# Sheet1.net
KiCad netlist of a schematic drawn in Altium Designer
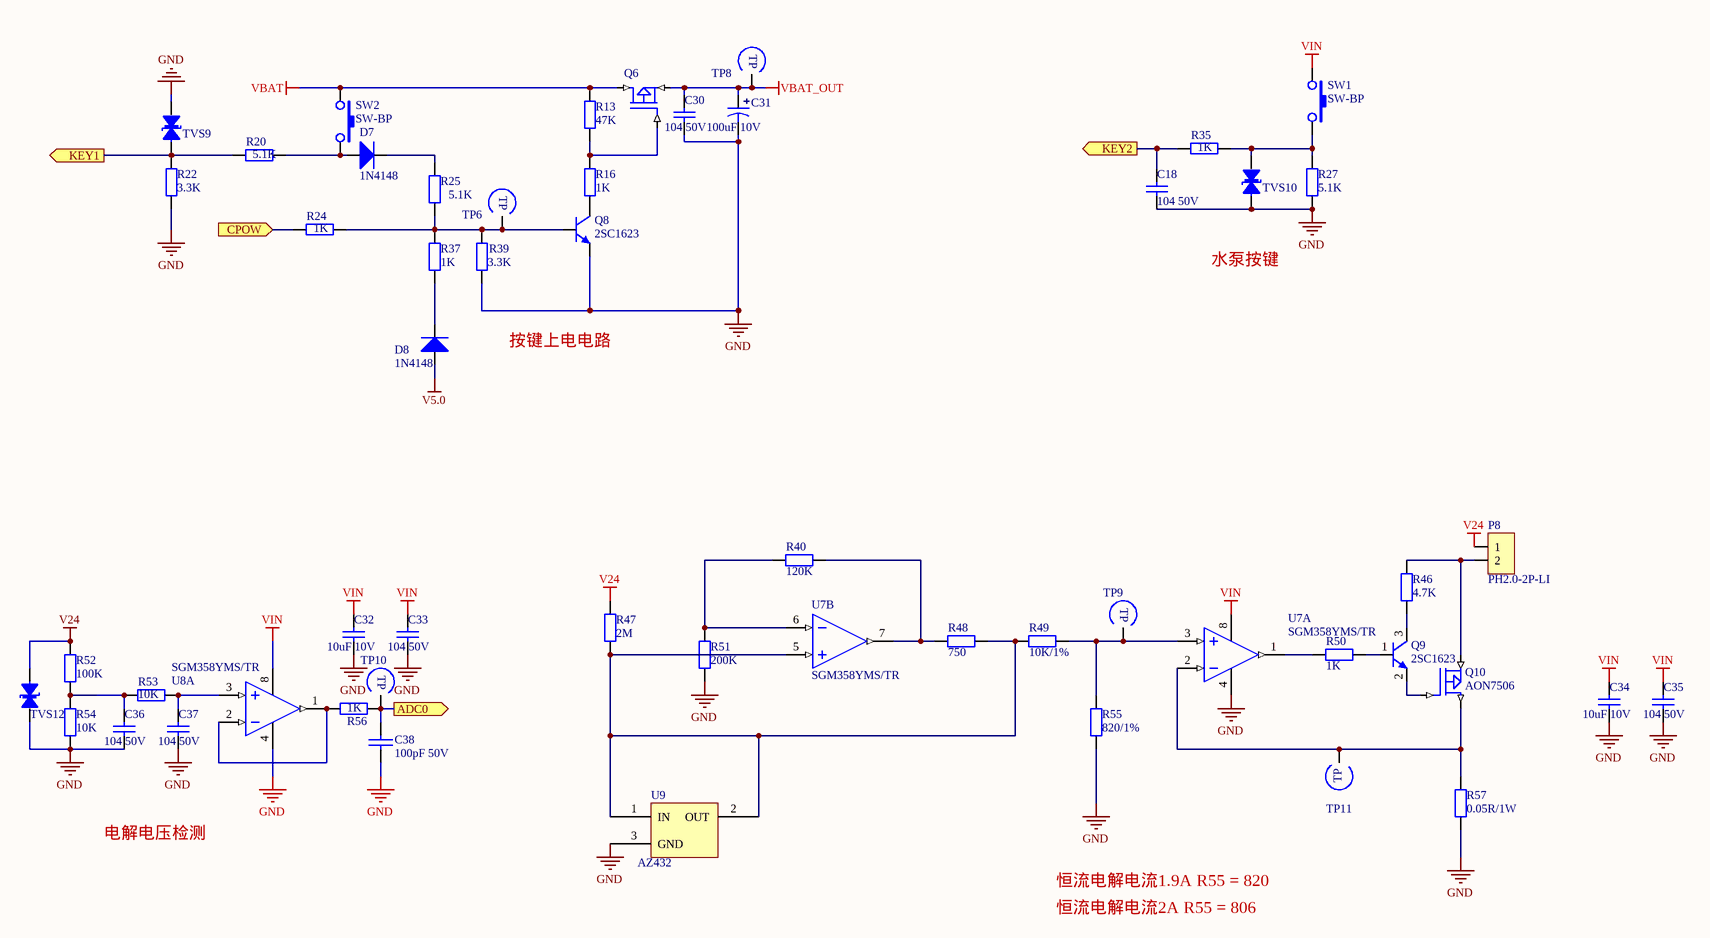
[diagram p0: Sheet1.SchDoc]

(export (version "E")
  (design (tool "Eeschema 10.0.6"))
  (components
    (comp (ref "C18")
      (value "104 50V")
      (footprint "SMD-0603C")
      (description "贴片电容 10%")
      (libsource (lib "XiaoyI") (part "CAP4"))
    )
    (comp (ref "C30")
      (value "104 50V")
      (footprint "SMD-0603C")
      (description "贴片电容 10%")
      (libsource (lib "XiaoyI") (part "CAP4"))
    )
    (comp (ref "C31")
      (value "100uF 10V")
      (footprint "SMD-3528-B")
      (description "钽电容")
      (libsource (lib "XiaoyI") (part "CAP2"))
    )
    (comp (ref "C32")
      (value "10uF 10V")
      (footprint "SMD-0603C")
      (description "贴片电容 10%")
      (libsource (lib "XiaoyI") (part "CAP4"))
    )
    (comp (ref "C33")
      (value "104 50V")
      (footprint "SMD-0603C")
      (description "贴片电容 10%")
      (libsource (lib "XiaoyI") (part "CAP4"))
    )
    (comp (ref "C34")
      (value "10uF 10V")
      (footprint "SMD-0603C")
      (description "贴片电容 10%")
      (libsource (lib "XiaoyI") (part "CAP4"))
    )
    (comp (ref "C35")
      (value "104 50V")
      (footprint "SMD-0603C")
      (description "贴片电容 10%")
      (libsource (lib "XiaoyI") (part "CAP4"))
    )
    (comp (ref "C36")
      (value "104 50V")
      (footprint "SMD-0603C")
      (description "贴片电容 10%")
      (libsource (lib "XiaoyI") (part "CAP4"))
    )
    (comp (ref "C37")
      (value "104 50V")
      (footprint "SMD-0603C")
      (description "贴片电容 10%")
      (libsource (lib "XiaoyI") (part "CAP4"))
    )
    (comp (ref "C38")
      (value "100pF 50V")
      (footprint "SMD-0603C")
      (description "贴片电容 10%")
      (libsource (lib "*") (part "CAP"))
    )
    (comp (ref "D7")
      (value "1N4148")
      (footprint "SOD-523")
      (description "小封装二极管")
      (libsource (lib "XiaoyI") (part "DIODE2"))
    )
    (comp (ref "D8")
      (value "1N4148")
      (footprint "SOD-523")
      (description "小封装二极管")
      (libsource (lib "XiaoyI") (part "DIODE2"))
    )
    (comp (ref "P8")
      (value "PH2.0-2P-LI")
      (footprint "PH2.0-2P-LI")
      (description "间距2.0mm 立贴 2Pin")
      (libsource (lib "XiaoyI") (part "SIP-2"))
    )
    (comp (ref "Q6")
      (value "AO3401")
      (footprint "SOT-23")
      (description "MOSFET P")
      (libsource (lib "ABB") (part "MOSFET P"))
    )
    (comp (ref "Q8")
      (value "2SC1623")
      (footprint "SOT-23")
      (description "NPN")
      (libsource (lib "") (part "NPN-1_1"))
    )
    (comp (ref "Q9")
      (value "2SC1623")
      (footprint "SOT-23")
      (description "NPN")
      (libsource (lib "XiaoyI") (part "NPN-1"))
    )
    (comp (ref "Q10")
      (value "AON7506")
      (footprint "DFN3*3-8")
      (description "MOSFET-P")
      (libsource (lib "XiaoyI") (part "MOSFET-P-B"))
    )
    (comp (ref "R13")
      (value "47K")
      (footprint "SMD-0603")
      (description "贴片电阻 5%")
      (libsource (lib "") (part "RES2_2"))
    )
    (comp (ref "R16")
      (value "1K")
      (footprint "SMD-0603")
      (description "贴片电阻 5%")
      (libsource (lib "XiaoyI") (part "RES2"))
    )
    (comp (ref "R20")
      (value "5.1K")
      (footprint "SMD-0603")
      (description "贴片电阻 5%")
      (libsource (lib "") (part "RES2_1"))
    )
    (comp (ref "R22")
      (value "3.3K")
      (footprint "SMD-0603")
      (description "贴片电阻 5%")
      (libsource (lib "XiaoyI") (part "RES2"))
    )
    (comp (ref "R24")
      (value "1K")
      (footprint "SMD-0603")
      (description "贴片电阻 5%")
      (libsource (lib "") (part "RES2_1"))
    )
    (comp (ref "R25")
      (value "5.1K")
      (footprint "SMD-0603")
      (description "贴片电阻 5%")
      (libsource (lib "XiaoyI") (part "RES2"))
    )
    (comp (ref "R27")
      (value "5.1K")
      (footprint "SMD-0603")
      (description "贴片电阻 5%")
      (libsource (lib "XiaoyI") (part "RES2"))
    )
    (comp (ref "R35")
      (value "1K")
      (footprint "SMD-0603")
      (description "贴片电阻 5%")
      (libsource (lib "") (part "RES2_1"))
    )
    (comp (ref "R37")
      (value "1K")
      (footprint "SMD-0603")
      (description "贴片电阻 5%")
      (libsource (lib "XiaoyI") (part "RES2"))
    )
    (comp (ref "R39")
      (value "3.3K")
      (footprint "SMD-0603")
      (description "贴片电阻 5%")
      (libsource (lib "XiaoyI") (part "RES2"))
    )
    (comp (ref "R40")
      (value "120K")
      (footprint "SMD-0603")
      (description "贴片电阻 1%")
      (libsource (lib "") (part "RES2_1"))
    )
    (comp (ref "R46")
      (value "4.7K")
      (footprint "SMD-0603")
      (description "贴片电阻 1%")
      (libsource (lib "XiaoyI") (part "RES2"))
    )
    (comp (ref "R47")
      (value "2M")
      (footprint "SMD-0603")
      (description "贴片电阻 1%")
      (libsource (lib "") (part "RES2_2"))
    )
    (comp (ref "R48")
      (value "750")
      (footprint "SMD-0603")
      (description "贴片电阻 1%")
      (libsource (lib "") (part "RES2_1"))
    )
    (comp (ref "R49")
      (value "10K/1%")
      (footprint "SMD-0603")
      (description "贴片电阻 1%")
      (libsource (lib "") (part "RES2_1"))
    )
    (comp (ref "R50")
      (value "1K")
      (footprint "SMD-0603")
      (description "贴片电阻 1%")
      (libsource (lib "") (part "RES2_1"))
    )
    (comp (ref "R51")
      (value "200K")
      (footprint "SMD-0603")
      (description "贴片电阻 1%")
      (libsource (lib "") (part "RES2_2"))
    )
    (comp (ref "R52")
      (value "100K")
      (footprint "SMD-0603")
      (description "贴片电阻 1%")
      (libsource (lib "ABB") (part "RES0"))
    )
    (comp (ref "R53")
      (value "10K")
      (footprint "SMD-0603")
      (description "贴片电阻 5%")
      (libsource (lib "") (part "RES0_1"))
    )
    (comp (ref "R54")
      (value "10K")
      (footprint "SMD-0603")
      (description "贴片电阻 1%")
      (libsource (lib "ABB") (part "RES0"))
    )
    (comp (ref "R55")
      (value "820/1%")
      (footprint "SMD-0603")
      (description "贴片电阻 1%")
      (libsource (lib "XiaoyI") (part "RES2"))
    )
    (comp (ref "R56")
      (value "1K")
      (footprint "SMD-0603")
      (description "贴片电阻 1%")
      (libsource (lib "") (part "RES2_3"))
    )
    (comp (ref "R57")
      (value "0.05R/1W")
      (footprint "SMD-1206")
      (description "贴片电阻 0.1%")
      (libsource (lib "XiaoyI") (part "RES2"))
    )
    (comp (ref "SW1")
      (value "SW-BP")
      (footprint "PB-3*6*3.5侧")
      (description "3*6*3.5侧贴按键(编带)")
      (libsource (lib "XiaoyI") (part "SW-BP"))
    )
    (comp (ref "SW2")
      (value "SW-BP")
      (footprint "PB-3*6*3.5侧")
      (description "3*6*3.5侧贴按键(编带)")
      (libsource (lib "XiaoyI") (part "SW-BP"))
    )
    (comp (ref "TP6")
      (value "testpoint")
      (footprint "TP")
      (description "测试点")
      (libsource (lib "XiaoyI") (part "TP-1"))
    )
    (comp (ref "TP8")
      (value "testpoint")
      (footprint "TP")
      (description "测试点")
      (libsource (lib "XiaoyI") (part "TP-1"))
    )
    (comp (ref "TP9")
      (value "testpoint")
      (footprint "TP")
      (description "测试点")
      (libsource (lib "XiaoyI") (part "TP-1"))
    )
    (comp (ref "TP10")
      (value "testpoint")
      (footprint "TP")
      (description "测试点")
      (libsource (lib "XiaoyI") (part "TP-1"))
    )
    (comp (ref "TP11")
      (value "testpoint")
      (footprint "TP")
      (description "测试点")
      (libsource (lib "XiaoyI") (part "TP-1"))
    )
    (comp (ref "TVS9")
      (value "ESD5Z5.0T1G")
      (footprint "SOD-523")
      (description "ESD二极管")
      (libsource (lib "XiaoyI") (part "TVS-1"))
    )
    (comp (ref "TVS10")
      (value "ESD5Z5.0T1G")
      (footprint "SOD-523")
      (description "ESD二极管")
      (libsource (lib "XiaoyI") (part "TVS-1"))
    )
    (comp (ref "TVS12")
      (value "NC")
      (footprint "SOD-123")
      (description "ESD二极管")
      (libsource (lib "") (part "TVS-1_1"))
    )
    (comp (ref "U7")
      (value "SGM358YMS/TR")
      (footprint "MSOP-8")
      (description "运放")
      (libsource (lib "XiaoyI") (part "LM358"))
    )
    (comp (ref "U8")
      (value "SGM358YMS/TR")
      (footprint "MSOP-8")
      (description "运放")
      (libsource (lib "XiaoyI") (part "LM358"))
    )
    (comp (ref "U9") (value "AZ432") (footprint "SOT-23") (libsource (lib "Schlib1") (part "REF3012")))
  )
  (nets
    (net (code "1") (name "/ADC0") (class "Default")
      (node (ref "C38") (pin "1") (pinfunction "1_1") (pintype "passive"))
      (node (ref "R56") (pin "1") (pinfunction "1_1") (pintype "passive"))
      (node (ref "TP10") (pin "1") (pinfunction "1_1") (pintype "passive"))
    )
    (net (code "2") (name "/CPOW") (class "Default")
      (node (ref "R24") (pin "1") (pinfunction "1_1") (pintype "passive"))
    )
    (net (code "3") (name "/KEY1") (class "Default")
      (node (ref "R20") (pin "1") (pinfunction "1_1") (pintype "passive"))
      (node (ref "R22") (pin "2") (pinfunction "2_2") (pintype "passive"))
      (node (ref "TVS9") (pin "2") (pinfunction "B_2") (pintype "passive"))
    )
    (net (code "4") (name "/KEY2") (class "Default")
      (node (ref "C18") (pin "2") (pinfunction "2_2") (pintype "passive"))
      (node (ref "R35") (pin "1") (pinfunction "1_1") (pintype "passive"))
    )
    (net (code "5") (name "GND") (class "Default")
      (node (ref "C18") (pin "1") (pinfunction "1_1") (pintype "passive"))
      (node (ref "C30") (pin "1") (pinfunction "1_1") (pintype "passive"))
      (node (ref "C31") (pin "2") (pinfunction "2_2") (pintype "passive"))
      (node (ref "C32") (pin "1") (pinfunction "1_1") (pintype "passive"))
      (node (ref "C33") (pin "1") (pinfunction "1_1") (pintype "passive"))
      (node (ref "C34") (pin "1") (pinfunction "1_1") (pintype "passive"))
      (node (ref "C35") (pin "1") (pinfunction "1_1") (pintype "passive"))
      (node (ref "C36") (pin "1") (pinfunction "1_1") (pintype "passive"))
      (node (ref "C37") (pin "1") (pinfunction "1_1") (pintype "passive"))
      (node (ref "C38") (pin "2") (pinfunction "2_2") (pintype "passive"))
      (node (ref "Q8") (pin "2") (pinfunction "E_2") (pintype "passive"))
      (node (ref "R22") (pin "1") (pinfunction "1_1") (pintype "passive"))
      (node (ref "R27") (pin "1") (pinfunction "1_1") (pintype "passive"))
      (node (ref "R39") (pin "1") (pinfunction "1_1") (pintype "passive"))
      (node (ref "R51") (pin "2") (pinfunction "2_2") (pintype "passive"))
      (node (ref "R54") (pin "1") (pinfunction "1_1") (pintype "passive"))
      (node (ref "R55") (pin "1") (pinfunction "1_1") (pintype "passive"))
      (node (ref "R57") (pin "1") (pinfunction "1_1") (pintype "passive"))
      (node (ref "TVS10") (pin "2") (pinfunction "B_2") (pintype "passive"))
      (node (ref "TVS12") (pin "1") (pinfunction "A_1") (pintype "passive"))
      (node (ref "TVS9") (pin "1") (pinfunction "A_1") (pintype "passive"))
      (node (ref "U7") (pin "4") (pinfunction "V-_4") (pintype "power_in"))
      (node (ref "U8") (pin "4") (pinfunction "V-_4") (pintype "power_in"))
      (node (ref "U9") (pin "3") (pinfunction "GND_3") (pintype "passive"))
    )
    (net (code "6") (name "Net-(C36-Pad2)") (class "Default")
      (node (ref "C36") (pin "2") (pinfunction "2_2") (pintype "passive"))
      (node (ref "R52") (pin "1") (pinfunction "1_1") (pintype "passive"))
      (node (ref "R53") (pin "2") (pinfunction "2_2") (pintype "passive"))
      (node (ref "R54") (pin "2") (pinfunction "2_2") (pintype "passive"))
    )
    (net (code "7") (name "Net-(D7-A)") (class "Default")
      (node (ref "D7") (pin "1") (pinfunction "A_1") (pintype "passive"))
      (node (ref "R20") (pin "2") (pinfunction "2_2") (pintype "passive"))
      (node (ref "SW2") (pin "2") (pinfunction "2_2") (pintype "passive"))
    )
    (net (code "8") (name "Net-(D7-K)") (class "Default")
      (node (ref "D7") (pin "2") (pinfunction "K_2") (pintype "passive"))
      (node (ref "R25") (pin "2") (pinfunction "2_2") (pintype "passive"))
    )
    (net (code "9") (name "Net-(D8-K)") (class "Default")
      (node (ref "D8") (pin "2") (pinfunction "K_2") (pintype "passive"))
      (node (ref "R37") (pin "1") (pinfunction "1_1") (pintype "passive"))
    )
    (net (code "10") (name "Net-(Q6-G)") (class "Default")
      (node (ref "Q6") (pin "1") (pinfunction "G_1") (pintype "input"))
      (node (ref "R13") (pin "2") (pinfunction "2_2") (pintype "passive"))
      (node (ref "R16") (pin "2") (pinfunction "2_2") (pintype "passive"))
    )
    (net (code "11") (name "Net-(Q8-B)") (class "Default")
      (node (ref "Q8") (pin "1") (pinfunction "B_1") (pintype "passive"))
      (node (ref "R24") (pin "2") (pinfunction "2_2") (pintype "passive"))
      (node (ref "R25") (pin "1") (pinfunction "1_1") (pintype "passive"))
      (node (ref "R37") (pin "2") (pinfunction "2_2") (pintype "passive"))
      (node (ref "R39") (pin "2") (pinfunction "2_2") (pintype "passive"))
      (node (ref "TP6") (pin "1") (pinfunction "1_1") (pintype "passive"))
    )
    (net (code "12") (name "Net-(Q9-B)") (class "Default")
      (node (ref "Q9") (pin "1") (pinfunction "B_1") (pintype "passive"))
      (node (ref "R50") (pin "2") (pinfunction "2_2") (pintype "passive"))
    )
    (net (code "13") (name "Net-(Q9-C)") (class "Default")
      (node (ref "Q9") (pin "3") (pinfunction "C_3") (pintype "passive"))
      (node (ref "R46") (pin "1") (pinfunction "1_1") (pintype "passive"))
    )
    (net (code "14") (name "Net-(Q10-D)") (class "Default")
      (node (ref "Q10") (pin "2") (pinfunction "D_2") (pintype "output"))
      (node (ref "R57") (pin "2") (pinfunction "2_2") (pintype "passive"))
      (node (ref "TP11") (pin "1") (pinfunction "1_1") (pintype "passive"))
      (node (ref "U7") (pin "2") (pinfunction "IN1-_2") (pintype "input"))
    )
    (net (code "15") (name "Net-(Q10-G)") (class "Default")
      (node (ref "Q10") (pin "1") (pinfunction "G_1") (pintype "input"))
      (node (ref "Q9") (pin "2") (pinfunction "E_2") (pintype "passive"))
    )
    (net (code "16") (name "Net-(Q10-S)") (class "Default")
      (node (ref "P8") (pin "2") (pinfunction "2_2") (pintype "passive"))
      (node (ref "Q10") (pin "3") (pinfunction "S_3") (pintype "input"))
      (node (ref "R46") (pin "2") (pinfunction "2_2") (pintype "passive"))
    )
    (net (code "17") (name "Net-(TVS10-A)") (class "Default")
      (node (ref "R27") (pin "2") (pinfunction "2_2") (pintype "passive"))
      (node (ref "R35") (pin "2") (pinfunction "2_2") (pintype "passive"))
      (node (ref "SW1") (pin "2") (pinfunction "2_2") (pintype "passive"))
      (node (ref "TVS10") (pin "1") (pinfunction "A_1") (pintype "passive"))
    )
    (net (code "18") (name "Net-(U7A-IN1+)") (class "Default")
      (node (ref "R49") (pin "2") (pinfunction "2_2") (pintype "passive"))
      (node (ref "R55") (pin "2") (pinfunction "2_2") (pintype "passive"))
      (node (ref "TP9") (pin "1") (pinfunction "1_1") (pintype "passive"))
      (node (ref "U7") (pin "3") (pinfunction "IN1+_3") (pintype "input"))
    )
    (net (code "19") (name "Net-(U7A-OUT1)") (class "Default")
      (node (ref "R50") (pin "1") (pinfunction "1_1") (pintype "passive"))
      (node (ref "U7") (pin "1") (pinfunction "OUT1_1") (pintype "output"))
    )
    (net (code "20") (name "Net-(U7B-IN2+)") (class "Default")
      (node (ref "R47") (pin "2") (pinfunction "2_2") (pintype "passive"))
      (node (ref "R48") (pin "2") (pinfunction "2_2") (pintype "passive"))
      (node (ref "R49") (pin "1") (pinfunction "1_1") (pintype "passive"))
      (node (ref "U7") (pin "5") (pinfunction "IN2+_5") (pintype "input"))
      (node (ref "U9") (pin "1") (pinfunction "IN_1") (pintype "passive"))
      (node (ref "U9") (pin "2") (pinfunction "OUT_2") (pintype "passive"))
    )
    (net (code "21") (name "Net-(U7B-IN2-)") (class "Default")
      (node (ref "R40") (pin "1") (pinfunction "1_1") (pintype "passive"))
      (node (ref "R51") (pin "1") (pinfunction "1_1") (pintype "passive"))
      (node (ref "U7") (pin "6") (pinfunction "IN2-_6") (pintype "input"))
    )
    (net (code "22") (name "Net-(U7B-OUT2)") (class "Default")
      (node (ref "R40") (pin "2") (pinfunction "2_2") (pintype "passive"))
      (node (ref "R48") (pin "1") (pinfunction "1_1") (pintype "passive"))
      (node (ref "U7") (pin "7") (pinfunction "OUT2_7") (pintype "output"))
    )
    (net (code "23") (name "Net-(U8A-IN1+)") (class "Default")
      (node (ref "C37") (pin "2") (pinfunction "2_2") (pintype "passive"))
      (node (ref "R53") (pin "1") (pinfunction "1_1") (pintype "passive"))
      (node (ref "U8") (pin "3") (pinfunction "IN1+_3") (pintype "input"))
    )
    (net (code "24") (name "Net-(U8A-IN1-)") (class "Default")
      (node (ref "R56") (pin "2") (pinfunction "2_2") (pintype "passive"))
      (node (ref "U8") (pin "1") (pinfunction "OUT1_1") (pintype "output"))
      (node (ref "U8") (pin "2") (pinfunction "IN1-_2") (pintype "input"))
    )
    (net (code "25") (name "V5.0") (class "Default")
      (node (ref "D8") (pin "1") (pinfunction "A_1") (pintype "passive"))
    )
    (net (code "26") (name "V24") (class "Default")
      (node (ref "P8") (pin "1") (pinfunction "1_1") (pintype "passive"))
      (node (ref "R47") (pin "1") (pinfunction "1_1") (pintype "passive"))
      (node (ref "R52") (pin "2") (pinfunction "2_2") (pintype "passive"))
      (node (ref "TVS12") (pin "2") (pinfunction "B_2") (pintype "passive"))
    )
    (net (code "27") (name "VBAT") (class "Default")
      (node (ref "Q6") (pin "2") (pinfunction "D_2") (pintype "input"))
      (node (ref "R13") (pin "1") (pinfunction "1_1") (pintype "passive"))
      (node (ref "SW2") (pin "1") (pinfunction "1_1") (pintype "passive"))
    )
    (net (code "28") (name "VBAT_OUT") (class "Default")
      (node (ref "C30") (pin "2") (pinfunction "2_2") (pintype "passive"))
      (node (ref "C31") (pin "1") (pinfunction "1_1") (pintype "passive"))
      (node (ref "Q6") (pin "3") (pinfunction "S_3") (pintype "input"))
      (node (ref "TP8") (pin "1") (pinfunction "1_1") (pintype "passive"))
    )
    (net (code "29") (name "VIN") (class "Default")
      (node (ref "C32") (pin "2") (pinfunction "2_2") (pintype "passive"))
      (node (ref "C33") (pin "2") (pinfunction "2_2") (pintype "passive"))
      (node (ref "C34") (pin "2") (pinfunction "2_2") (pintype "passive"))
      (node (ref "C35") (pin "2") (pinfunction "2_2") (pintype "passive"))
      (node (ref "SW1") (pin "1") (pinfunction "1_1") (pintype "passive"))
      (node (ref "U7") (pin "8") (pinfunction "V+_8") (pintype "power_in"))
      (node (ref "U8") (pin "8") (pinfunction "V+_8") (pintype "power_in"))
    )
    (net (code "30") (name "unconnected-(Q8-C-Pad3)") (class "Default")
      (node (ref "Q8") (pin "3") (pinfunction "C_3") (pintype "passive"))
    )
    (net (code "31") (name "unconnected-(R16-Pad1)") (class "Default")
      (node (ref "R16") (pin "1") (pinfunction "1_1") (pintype "passive"))
    )
  )
)
